# design.net
KiCad netlist of a schematic drawn in Altium Designer
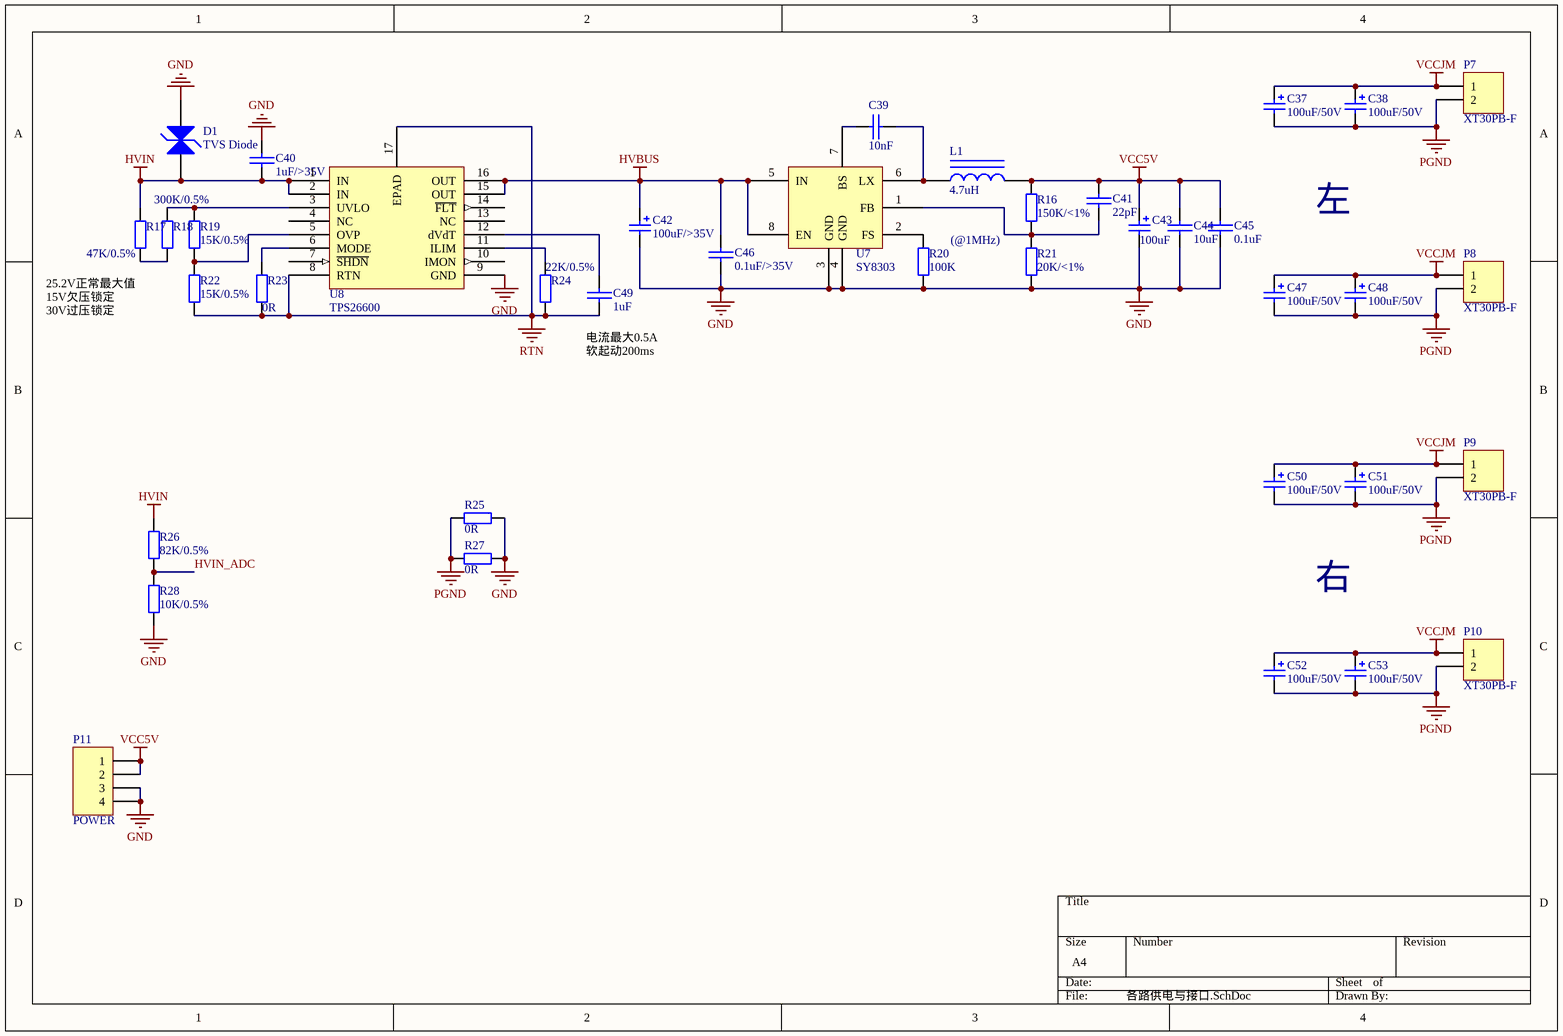
[diagram p0: 各路供电与接口.SchDoc]

(export (version "E")
  (design (tool "Eeschema 10.0.6"))
  (components
    (comp (ref "C37")
      (value "100uF/50V")
      (footprint "CS 6*6 - R")
      (description "Low ESR required")
      (fields (field (name "PUBLISHER") "Altium Limited"))
      (libsource (lib "Miscellaneous Devices") (part "Cap Pol2"))
    )
    (comp (ref "C38")
      (value "100uF/50V")
      (footprint "CS 6*6 - R")
      (description "Low ESR required")
      (fields (field (name "PUBLISHER") "Altium Limited"))
      (libsource (lib "Miscellaneous Devices") (part "Cap Pol2"))
    )
    (comp (ref "C39")
      (value "10nF")
      (footprint "C0805_M")
      (description "Capacitor")
      (libsource (lib "*") (part "CAP"))
    )
    (comp (ref "C40")
      (value "1uF/>35V")
      (footprint "C0805_M")
      (description "Capacitor")
      (libsource (lib "*") (part "CAP"))
    )
    (comp (ref "C41")
      (value "22pF")
      (footprint "C0805_M")
      (description "Capacitor")
      (libsource (lib "*") (part "CAP"))
    )
    (comp (ref "C42")
      (value "100uF/>35V")
      (footprint "CS 6*6 - R")
      (description "固态电容")
      (fields (field (name "PUBLISHER") "Altium Limited"))
      (libsource (lib "Miscellaneous Devices") (part "Cap Pol2"))
    )
    (comp (ref "C43")
      (value "100uF")
      (footprint "CS 6*6 - R")
      (description "固态电容")
      (fields (field (name "PUBLISHER") "Altium Limited"))
      (libsource (lib "Miscellaneous Devices") (part "Cap Pol2"))
    )
    (comp (ref "C44")
      (value "10uF")
      (footprint "C0805_M")
      (description "Capacitor")
      (libsource (lib "*") (part "CAP"))
    )
    (comp (ref "C45")
      (value "0.1uF")
      (footprint "C0805_M")
      (description "Capacitor")
      (libsource (lib "*") (part "CAP"))
    )
    (comp (ref "C46")
      (value "0.1uF/>35V")
      (footprint "C0805_M")
      (description "Capacitor")
      (libsource (lib "*") (part "CAP"))
    )
    (comp (ref "C47")
      (value "100uF/50V")
      (footprint "CS 6*6 - R")
      (description "Low ESR required")
      (fields (field (name "PUBLISHER") "Altium Limited"))
      (libsource (lib "Miscellaneous Devices") (part "Cap Pol2"))
    )
    (comp (ref "C48")
      (value "100uF/50V")
      (footprint "CS 6*6 - R")
      (description "Low ESR required")
      (fields (field (name "PUBLISHER") "Altium Limited"))
      (libsource (lib "Miscellaneous Devices") (part "Cap Pol2"))
    )
    (comp (ref "C49")
      (value "1uF")
      (footprint "C0805_M")
      (description "Capacitor")
      (libsource (lib "*") (part "CAP"))
    )
    (comp (ref "C50")
      (value "100uF/50V")
      (footprint "CS 6*6 - R")
      (description "Low ESR required")
      (fields (field (name "PUBLISHER") "Altium Limited"))
      (libsource (lib "Miscellaneous Devices") (part "Cap Pol2"))
    )
    (comp (ref "C51")
      (value "100uF/50V")
      (footprint "CS 6*6 - R")
      (description "Low ESR required")
      (fields (field (name "PUBLISHER") "Altium Limited"))
      (libsource (lib "Miscellaneous Devices") (part "Cap Pol2"))
    )
    (comp (ref "C52")
      (value "100uF/50V")
      (footprint "CS 6*6 - R")
      (description "Low ESR required")
      (fields (field (name "PUBLISHER") "Altium Limited"))
      (libsource (lib "Miscellaneous Devices") (part "Cap Pol2"))
    )
    (comp (ref "C53")
      (value "100uF/50V")
      (footprint "CS 6*6 - R")
      (description "Low ESR required")
      (fields (field (name "PUBLISHER") "Altium Limited"))
      (libsource (lib "Miscellaneous Devices") (part "Cap Pol2"))
    )
    (comp (ref "D1")
      (value "TVS Diode")
      (footprint "1.07-二极管、整流桥:SMB")
      (libsource (lib "XL6005") (part "TVS"))
    )
    (comp (ref "L1")
      (value "4.7uH")
      (footprint "L-SMD-0630")
      (description "Magnetic-Core Inductor")
      (fields (field (name "PUBLISHER") "Altium Limited"))
      (libsource (lib "Miscellaneous Devices") (part "Inductor Iron"))
    )
    (comp (ref "P7")
      (value "XT30PB-F")
      (footprint "XT30PB-F")
      (description "Header, 2-Pin")
      (fields (field (name "PUBLISHER") "Altium Limited"))
      (libsource (lib "Miscellaneous Connectors") (part "Header 2"))
    )
    (comp (ref "P8")
      (value "XT30PB-F")
      (footprint "XT30PB-F")
      (description "Header, 2-Pin")
      (fields (field (name "PUBLISHER") "Altium Limited"))
      (libsource (lib "Miscellaneous Connectors") (part "Header 2"))
    )
    (comp (ref "P9")
      (value "XT30PB-F")
      (footprint "XT30PB-F")
      (description "Header, 2-Pin")
      (fields (field (name "PUBLISHER") "Altium Limited"))
      (libsource (lib "Miscellaneous Connectors") (part "Header 2"))
    )
    (comp (ref "P10")
      (value "XT30PB-F")
      (footprint "XT30PB-F")
      (description "Header, 2-Pin")
      (fields (field (name "PUBLISHER") "Altium Limited"))
      (libsource (lib "Miscellaneous Connectors") (part "Header 2"))
    )
    (comp (ref "P11")
      (value "POWER")
      (footprint "XH2.54-LI-4P")
      (description "Header, 4-Pin")
      (fields (field (name "PUBLISHER") "Altium Limited"))
      (libsource (lib "Miscellaneous Connectors") (part "Header 4"))
    )
    (comp (ref "R16")
      (value "150K/<1%")
      (footprint "R0805_M")
      (description "Resistor")
      (fields (field (name "PUBLISHER") "Altium Limited"))
      (libsource (lib "Miscellaneous Devices") (part "Res2"))
    )
    (comp (ref "R17")
      (value "47K/0.5%")
      (footprint "R0805_M")
      (description "Resistor")
      (fields (field (name "PUBLISHER") "Altium Limited"))
      (libsource (lib "Miscellaneous Devices") (part "Res2"))
    )
    (comp (ref "R18")
      (value "300K/0.5%")
      (footprint "R0805_M")
      (description "Resistor")
      (fields (field (name "PUBLISHER") "Altium Limited"))
      (libsource (lib "Miscellaneous Devices") (part "Res2"))
    )
    (comp (ref "R19")
      (value "15K/0.5%")
      (footprint "R0805_M")
      (description "Resistor")
      (fields (field (name "PUBLISHER") "Altium Limited"))
      (libsource (lib "Miscellaneous Devices") (part "Res2"))
    )
    (comp (ref "R20")
      (value "100K")
      (footprint "R0805_M")
      (description "Resistor")
      (fields (field (name "PUBLISHER") "Altium Limited"))
      (libsource (lib "Miscellaneous Devices") (part "Res2"))
    )
    (comp (ref "R21")
      (value "20K/<1%")
      (footprint "R0805_M")
      (description "Resistor")
      (fields (field (name "PUBLISHER") "Altium Limited"))
      (libsource (lib "Miscellaneous Devices") (part "Res2"))
    )
    (comp (ref "R22")
      (value "15K/0.5%")
      (footprint "R0805_M")
      (description "Resistor")
      (fields (field (name "PUBLISHER") "Altium Limited"))
      (libsource (lib "Miscellaneous Devices") (part "Res2"))
    )
    (comp (ref "R23")
      (value "0R")
      (footprint "R0805_M")
      (description "Resistor")
      (fields (field (name "PUBLISHER") "Altium Limited"))
      (libsource (lib "Miscellaneous Devices") (part "Res2"))
    )
    (comp (ref "R24")
      (value "22K/0.5%")
      (footprint "R0805_M")
      (description "Resistor")
      (fields (field (name "PUBLISHER") "Altium Limited"))
      (libsource (lib "Miscellaneous Devices") (part "Res2"))
    )
    (comp (ref "R25")
      (value "0R")
      (footprint "R0805_M")
      (description "Resistor")
      (fields (field (name "PUBLISHER") "Altium Limited"))
      (libsource (lib "") (part "Res2_1"))
    )
    (comp (ref "R26")
      (value "82K/0.5%")
      (footprint "R0805_M")
      (description "Resistor")
      (fields (field (name "PUBLISHER") "Altium Limited"))
      (libsource (lib "Miscellaneous Devices") (part "Res2"))
    )
    (comp (ref "R27")
      (value "0R")
      (footprint "R0805_M")
      (description "Resistor")
      (fields (field (name "PUBLISHER") "Altium Limited"))
      (libsource (lib "") (part "Res2_1"))
    )
    (comp (ref "R28")
      (value "10K/0.5%")
      (footprint "R0805_M")
      (description "Resistor")
      (fields (field (name "PUBLISHER") "Altium Limited"))
      (libsource (lib "Miscellaneous Devices") (part "Res2"))
    )
    (comp (ref "U7") (value "SY8303") (footprint "SOT23-8L") (libsource (lib "7688A原理图封装") (part "SY8303")))
    (comp (ref "U8") (value "TPS26600") (footprint "ETSSOP16_M") (libsource (lib "XL6005") (part "TPS26600")))
  )
  (nets
    (net (code "1") (name "/HVIN_ADC") (class "Default")
      (node (ref "R26") (pin "2") (pinfunction "2_2") (pintype "passive"))
      (node (ref "R28") (pin "1") (pinfunction "1_1") (pintype "passive"))
    )
    (net (code "2") (name "GND") (class "Default")
      (node (ref "C40") (pin "2") (pinfunction "2_2") (pintype "passive"))
      (node (ref "C42") (pin "2") (pinfunction "2_2") (pintype "passive"))
      (node (ref "C43") (pin "2") (pinfunction "2_2") (pintype "passive"))
      (node (ref "C44") (pin "1") (pinfunction "1_1") (pintype "passive"))
      (node (ref "C45") (pin "1") (pinfunction "1_1") (pintype "passive"))
      (node (ref "C46") (pin "1") (pinfunction "1_1") (pintype "passive"))
      (node (ref "D1") (pin "2") (pinfunction "K_2") (pintype "passive"))
      (node (ref "P11") (pin "3") (pinfunction "3_3") (pintype "passive"))
      (node (ref "P11") (pin "4") (pinfunction "4_4") (pintype "passive"))
      (node (ref "R20") (pin "2") (pinfunction "2_2") (pintype "passive"))
      (node (ref "R21") (pin "2") (pinfunction "2_2") (pintype "passive"))
      (node (ref "R25") (pin "2") (pinfunction "2_2") (pintype "passive"))
      (node (ref "R27") (pin "2") (pinfunction "2_2") (pintype "passive"))
      (node (ref "R28") (pin "2") (pinfunction "2_2") (pintype "passive"))
      (node (ref "U7") (pin "3") (pinfunction "GND_3") (pintype "passive"))
      (node (ref "U7") (pin "4") (pinfunction "GND_4") (pintype "passive"))
      (node (ref "U8") (pin "9") (pinfunction "GND_9") (pintype "passive"))
    )
    (net (code "3") (name "HVBUS") (class "Default")
      (node (ref "C42") (pin "1") (pinfunction "1_1") (pintype "passive"))
      (node (ref "C46") (pin "2") (pinfunction "2_2") (pintype "passive"))
      (node (ref "U7") (pin "5") (pinfunction "IN_5") (pintype "passive"))
      (node (ref "U7") (pin "8") (pinfunction "EN_8") (pintype "passive"))
      (node (ref "U8") (pin "15") (pinfunction "OUT_15") (pintype "passive"))
      (node (ref "U8") (pin "16") (pinfunction "OUT_16") (pintype "passive"))
    )
    (net (code "4") (name "HVIN") (class "Default")
      (node (ref "C40") (pin "1") (pinfunction "1_1") (pintype "passive"))
      (node (ref "D1") (pin "1") (pinfunction "A_1") (pintype "passive"))
      (node (ref "R17") (pin "1") (pinfunction "1_1") (pintype "passive"))
      (node (ref "R26") (pin "1") (pinfunction "1_1") (pintype "passive"))
      (node (ref "U8") (pin "1") (pinfunction "IN_1") (pintype "passive"))
      (node (ref "U8") (pin "2") (pinfunction "IN_2") (pintype "passive"))
    )
    (net (code "5") (name "Net-(R17-Pad2)") (class "Default")
      (node (ref "R17") (pin "2") (pinfunction "2_2") (pintype "passive"))
      (node (ref "R18") (pin "2") (pinfunction "2_2") (pintype "passive"))
    )
    (net (code "6") (name "Net-(U7-BS)") (class "Default")
      (node (ref "C39") (pin "1") (pinfunction "1_1") (pintype "passive"))
      (node (ref "U7") (pin "7") (pinfunction "BS_7") (pintype "passive"))
    )
    (net (code "7") (name "Net-(U7-FB)") (class "Default")
      (node (ref "C41") (pin "1") (pinfunction "1_1") (pintype "passive"))
      (node (ref "R16") (pin "2") (pinfunction "2_2") (pintype "passive"))
      (node (ref "R21") (pin "1") (pinfunction "1_1") (pintype "passive"))
      (node (ref "U7") (pin "1") (pinfunction "FB_1") (pintype "passive"))
    )
    (net (code "8") (name "Net-(U7-FS)") (class "Default")
      (node (ref "R20") (pin "1") (pinfunction "1_1") (pintype "passive"))
      (node (ref "U7") (pin "2") (pinfunction "FS_2") (pintype "passive"))
    )
    (net (code "9") (name "Net-(U7-LX)") (class "Default")
      (node (ref "C39") (pin "2") (pinfunction "2_2") (pintype "passive"))
      (node (ref "L1") (pin "1") (pinfunction "1_1") (pintype "passive"))
      (node (ref "U7") (pin "6") (pinfunction "LX_6") (pintype "passive"))
    )
    (net (code "10") (name "Net-(U8-ILIM)") (class "Default")
      (node (ref "R24") (pin "1") (pinfunction "1_1") (pintype "passive"))
      (node (ref "U8") (pin "11") (pinfunction "ILIM_11") (pintype "passive"))
    )
    (net (code "11") (name "Net-(U8-MODE)") (class "Default")
      (node (ref "R23") (pin "1") (pinfunction "1_1") (pintype "passive"))
      (node (ref "U8") (pin "6") (pinfunction "MODE_6") (pintype "passive"))
    )
    (net (code "12") (name "Net-(U8-OVP)") (class "Default")
      (node (ref "R19") (pin "2") (pinfunction "2_2") (pintype "passive"))
      (node (ref "R22") (pin "1") (pinfunction "1_1") (pintype "passive"))
      (node (ref "U8") (pin "5") (pinfunction "OVP_5") (pintype "passive"))
    )
    (net (code "13") (name "Net-(U8-UVLO)") (class "Default")
      (node (ref "R18") (pin "1") (pinfunction "1_1") (pintype "passive"))
      (node (ref "R19") (pin "1") (pinfunction "1_1") (pintype "passive"))
      (node (ref "U8") (pin "3") (pinfunction "UVLO_3") (pintype "passive"))
    )
    (net (code "14") (name "Net-(U8-dVdT)") (class "Default")
      (node (ref "C49") (pin "1") (pinfunction "1_1") (pintype "passive"))
      (node (ref "U8") (pin "12") (pinfunction "dVdT_12") (pintype "passive"))
    )
    (net (code "15") (name "PGND") (class "Default")
      (node (ref "C37") (pin "2") (pinfunction "2_2") (pintype "passive"))
      (node (ref "C38") (pin "2") (pinfunction "2_2") (pintype "passive"))
      (node (ref "C47") (pin "2") (pinfunction "2_2") (pintype "passive"))
      (node (ref "C48") (pin "2") (pinfunction "2_2") (pintype "passive"))
      (node (ref "C50") (pin "2") (pinfunction "2_2") (pintype "passive"))
      (node (ref "C51") (pin "2") (pinfunction "2_2") (pintype "passive"))
      (node (ref "C52") (pin "2") (pinfunction "2_2") (pintype "passive"))
      (node (ref "C53") (pin "2") (pinfunction "2_2") (pintype "passive"))
      (node (ref "P10") (pin "2") (pinfunction "2_2") (pintype "passive"))
      (node (ref "P7") (pin "2") (pinfunction "2_2") (pintype "passive"))
      (node (ref "P8") (pin "2") (pinfunction "2_2") (pintype "passive"))
      (node (ref "P9") (pin "2") (pinfunction "2_2") (pintype "passive"))
      (node (ref "R25") (pin "1") (pinfunction "1_1") (pintype "passive"))
      (node (ref "R27") (pin "1") (pinfunction "1_1") (pintype "passive"))
    )
    (net (code "16") (name "RTN") (class "Default")
      (node (ref "C49") (pin "2") (pinfunction "2_2") (pintype "passive"))
      (node (ref "R22") (pin "2") (pinfunction "2_2") (pintype "passive"))
      (node (ref "R23") (pin "2") (pinfunction "2_2") (pintype "passive"))
      (node (ref "R24") (pin "2") (pinfunction "2_2") (pintype "passive"))
      (node (ref "U8") (pin "17") (pinfunction "EPAD_17") (pintype "passive"))
      (node (ref "U8") (pin "8") (pinfunction "RTN_8") (pintype "passive"))
    )
    (net (code "17") (name "VCC5V") (class "Default")
      (node (ref "C41") (pin "2") (pinfunction "2_2") (pintype "passive"))
      (node (ref "C43") (pin "1") (pinfunction "1_1") (pintype "passive"))
      (node (ref "C44") (pin "2") (pinfunction "2_2") (pintype "passive"))
      (node (ref "C45") (pin "2") (pinfunction "2_2") (pintype "passive"))
      (node (ref "L1") (pin "2") (pinfunction "2_2") (pintype "passive"))
      (node (ref "P11") (pin "1") (pinfunction "1_1") (pintype "passive"))
      (node (ref "P11") (pin "2") (pinfunction "2_2") (pintype "passive"))
      (node (ref "R16") (pin "1") (pinfunction "1_1") (pintype "passive"))
    )
    (net (code "18") (name "VCCJM") (class "Default")
      (node (ref "C37") (pin "1") (pinfunction "1_1") (pintype "passive"))
      (node (ref "C38") (pin "1") (pinfunction "1_1") (pintype "passive"))
      (node (ref "C47") (pin "1") (pinfunction "1_1") (pintype "passive"))
      (node (ref "C48") (pin "1") (pinfunction "1_1") (pintype "passive"))
      (node (ref "C50") (pin "1") (pinfunction "1_1") (pintype "passive"))
      (node (ref "C51") (pin "1") (pinfunction "1_1") (pintype "passive"))
      (node (ref "C52") (pin "1") (pinfunction "1_1") (pintype "passive"))
      (node (ref "C53") (pin "1") (pinfunction "1_1") (pintype "passive"))
      (node (ref "P10") (pin "1") (pinfunction "1_1") (pintype "passive"))
      (node (ref "P7") (pin "1") (pinfunction "1_1") (pintype "passive"))
      (node (ref "P8") (pin "1") (pinfunction "1_1") (pintype "passive"))
      (node (ref "P9") (pin "1") (pinfunction "1_1") (pintype "passive"))
    )
    (net (code "19") (name "unconnected-(U8-IMON-Pad10)") (class "Default")
      (node (ref "U8") (pin "10") (pinfunction "IMON_10") (pintype "output"))
    )
    (net (code "20") (name "unconnected-(U8-NC-Pad4)") (class "Default")
      (node (ref "U8") (pin "4") (pinfunction "NC_4") (pintype "passive"))
    )
    (net (code "21") (name "unconnected-(U8-NC-Pad13)") (class "Default")
      (node (ref "U8") (pin "13") (pinfunction "NC_13") (pintype "passive"))
    )
    (net (code "22") (name "unconnected-(U8-~{FLT}-Pad14)") (class "Default")
      (node (ref "U8") (pin "14") (pinfunction "~{FLT}_14") (pintype "output"))
    )
    (net (code "23") (name "unconnected-(U8-~{SHDN}-Pad7)") (class "Default")
      (node (ref "U8") (pin "7") (pinfunction "~{SHDN}_7") (pintype "input"))
    )
  )
)
